# Power.net
KiCad netlist of a schematic drawn in Altium Designer
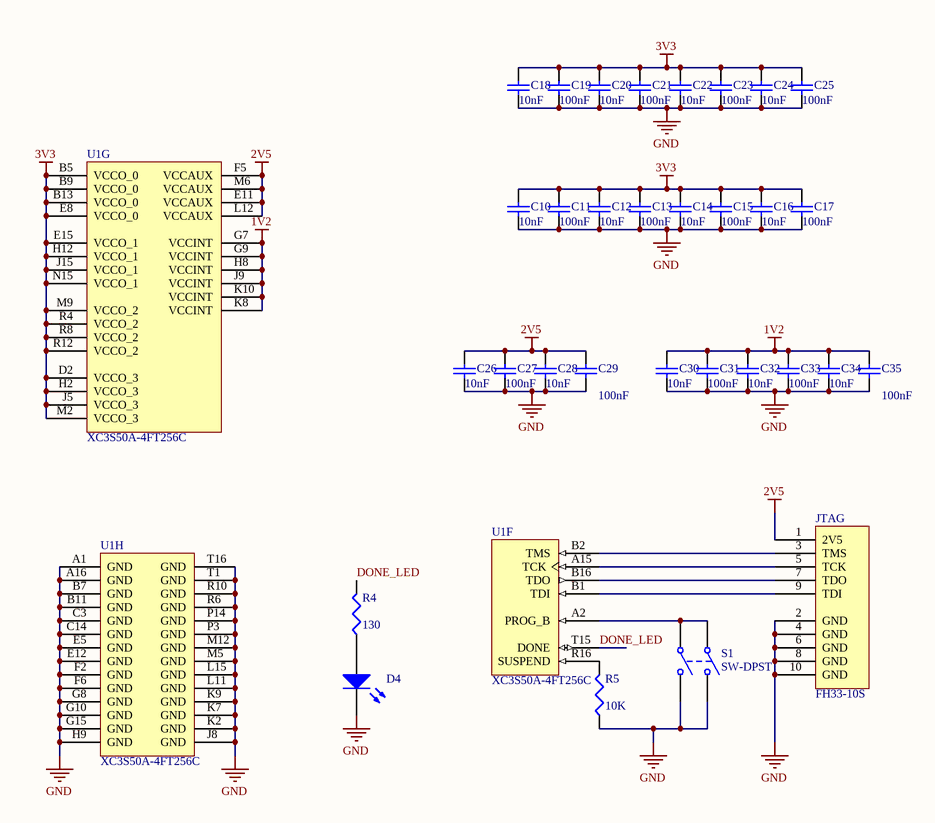
[diagram p0: Power.SchDoc]

(export (version "E")
  (design (tool "Eeschema 10.0.6"))
  (components
    (comp (ref "C10")
      (value "10nF")
      (footprint "0402")
      (description "Capacitor (Semiconductor SIM Model)")
      (fields (field (name "Comment") "Cap Semi") (field (name "PUBLISHER") "Altium Limited"))
      (libsource (lib "Miscellaneous Devices") (part "Cap Semi"))
    )
    (comp (ref "C11")
      (value "100nF")
      (footprint "0402")
      (description "Capacitor (Semiconductor SIM Model)")
      (fields (field (name "Comment") "Cap Semi") (field (name "PUBLISHER") "Altium Limited"))
      (libsource (lib "Miscellaneous Devices") (part "Cap Semi"))
    )
    (comp (ref "C12")
      (value "10nF")
      (footprint "0402")
      (description "Capacitor (Semiconductor SIM Model)")
      (fields (field (name "Comment") "Cap Semi") (field (name "PUBLISHER") "Altium Limited"))
      (libsource (lib "Miscellaneous Devices") (part "Cap Semi"))
    )
    (comp (ref "C13")
      (value "100nF")
      (footprint "0402")
      (description "Capacitor (Semiconductor SIM Model)")
      (fields (field (name "Comment") "Cap Semi") (field (name "PUBLISHER") "Altium Limited"))
      (libsource (lib "Miscellaneous Devices") (part "Cap Semi"))
    )
    (comp (ref "C14")
      (value "10nF")
      (footprint "0402")
      (description "Capacitor (Semiconductor SIM Model)")
      (fields (field (name "Comment") "Cap Semi") (field (name "PUBLISHER") "Altium Limited"))
      (libsource (lib "Miscellaneous Devices") (part "Cap Semi"))
    )
    (comp (ref "C15")
      (value "100nF")
      (footprint "0402")
      (description "Capacitor (Semiconductor SIM Model)")
      (fields (field (name "Comment") "Cap Semi") (field (name "PUBLISHER") "Altium Limited"))
      (libsource (lib "Miscellaneous Devices") (part "Cap Semi"))
    )
    (comp (ref "C16")
      (value "10nF")
      (footprint "0402")
      (description "Capacitor (Semiconductor SIM Model)")
      (fields (field (name "Comment") "Cap Semi") (field (name "PUBLISHER") "Altium Limited"))
      (libsource (lib "Miscellaneous Devices") (part "Cap Semi"))
    )
    (comp (ref "C17")
      (value "100nF")
      (footprint "0402")
      (description "Capacitor (Semiconductor SIM Model)")
      (fields (field (name "Comment") "Cap Semi") (field (name "PUBLISHER") "Altium Limited"))
      (libsource (lib "Miscellaneous Devices") (part "Cap Semi"))
    )
    (comp (ref "C18")
      (value "10nF")
      (footprint "0402")
      (description "Capacitor (Semiconductor SIM Model)")
      (fields (field (name "Comment") "Cap Semi") (field (name "PUBLISHER") "Altium Limited"))
      (libsource (lib "Miscellaneous Devices") (part "Cap Semi"))
    )
    (comp (ref "C19")
      (value "100nF")
      (footprint "0402")
      (description "Capacitor (Semiconductor SIM Model)")
      (fields (field (name "Comment") "Cap Semi") (field (name "PUBLISHER") "Altium Limited"))
      (libsource (lib "Miscellaneous Devices") (part "Cap Semi"))
    )
    (comp (ref "C20")
      (value "10nF")
      (footprint "0402")
      (description "Capacitor (Semiconductor SIM Model)")
      (fields (field (name "Comment") "Cap Semi") (field (name "PUBLISHER") "Altium Limited"))
      (libsource (lib "Miscellaneous Devices") (part "Cap Semi"))
    )
    (comp (ref "C21")
      (value "100nF")
      (footprint "0402")
      (description "Capacitor (Semiconductor SIM Model)")
      (fields (field (name "Comment") "Cap Semi") (field (name "PUBLISHER") "Altium Limited"))
      (libsource (lib "Miscellaneous Devices") (part "Cap Semi"))
    )
    (comp (ref "C22")
      (value "10nF")
      (footprint "0402")
      (description "Capacitor (Semiconductor SIM Model)")
      (fields (field (name "Comment") "Cap Semi") (field (name "PUBLISHER") "Altium Limited"))
      (libsource (lib "Miscellaneous Devices") (part "Cap Semi"))
    )
    (comp (ref "C23")
      (value "100nF")
      (footprint "0402")
      (description "Capacitor (Semiconductor SIM Model)")
      (fields (field (name "Comment") "Cap Semi") (field (name "PUBLISHER") "Altium Limited"))
      (libsource (lib "Miscellaneous Devices") (part "Cap Semi"))
    )
    (comp (ref "C24")
      (value "10nF")
      (footprint "0402")
      (description "Capacitor (Semiconductor SIM Model)")
      (fields (field (name "Comment") "Cap Semi") (field (name "PUBLISHER") "Altium Limited"))
      (libsource (lib "Miscellaneous Devices") (part "Cap Semi"))
    )
    (comp (ref "C25")
      (value "100nF")
      (footprint "0402")
      (description "Capacitor (Semiconductor SIM Model)")
      (fields (field (name "Comment") "Cap Semi") (field (name "PUBLISHER") "Altium Limited"))
      (libsource (lib "Miscellaneous Devices") (part "Cap Semi"))
    )
    (comp (ref "C26")
      (value "10nF")
      (footprint "0402")
      (description "Capacitor (Semiconductor SIM Model)")
      (fields (field (name "Comment") "Cap Semi") (field (name "PUBLISHER") "Altium Limited"))
      (libsource (lib "Miscellaneous Devices") (part "Cap Semi"))
    )
    (comp (ref "C27")
      (value "100nF")
      (footprint "0402")
      (description "Capacitor (Semiconductor SIM Model)")
      (fields (field (name "Comment") "Cap Semi") (field (name "PUBLISHER") "Altium Limited"))
      (libsource (lib "Miscellaneous Devices") (part "Cap Semi"))
    )
    (comp (ref "C28")
      (value "10nF")
      (footprint "0402")
      (description "Capacitor (Semiconductor SIM Model)")
      (fields (field (name "Comment") "Cap Semi") (field (name "PUBLISHER") "Altium Limited"))
      (libsource (lib "Miscellaneous Devices") (part "Cap Semi"))
    )
    (comp (ref "C29")
      (value "100nF")
      (footprint "0402")
      (description "Capacitor (Semiconductor SIM Model)")
      (fields (field (name "Comment") "Cap Semi") (field (name "PUBLISHER") "Altium Limited"))
      (libsource (lib "Miscellaneous Devices") (part "Cap Semi"))
    )
    (comp (ref "C30")
      (value "10nF")
      (footprint "0402")
      (description "Capacitor (Semiconductor SIM Model)")
      (fields (field (name "Comment") "Cap Semi") (field (name "PUBLISHER") "Altium Limited"))
      (libsource (lib "Miscellaneous Devices") (part "Cap Semi"))
    )
    (comp (ref "C31")
      (value "100nF")
      (footprint "0402")
      (description "Capacitor (Semiconductor SIM Model)")
      (fields (field (name "Comment") "Cap Semi") (field (name "PUBLISHER") "Altium Limited"))
      (libsource (lib "Miscellaneous Devices") (part "Cap Semi"))
    )
    (comp (ref "C32")
      (value "10nF")
      (footprint "0402")
      (description "Capacitor (Semiconductor SIM Model)")
      (fields (field (name "Comment") "Cap Semi") (field (name "PUBLISHER") "Altium Limited"))
      (libsource (lib "Miscellaneous Devices") (part "Cap Semi"))
    )
    (comp (ref "C33")
      (value "100nF")
      (footprint "0402")
      (description "Capacitor (Semiconductor SIM Model)")
      (fields (field (name "Comment") "Cap Semi") (field (name "PUBLISHER") "Altium Limited"))
      (libsource (lib "Miscellaneous Devices") (part "Cap Semi"))
    )
    (comp (ref "C34")
      (value "10nF")
      (footprint "0402")
      (description "Capacitor (Semiconductor SIM Model)")
      (fields (field (name "Comment") "Cap Semi") (field (name "PUBLISHER") "Altium Limited"))
      (libsource (lib "Miscellaneous Devices") (part "Cap Semi"))
    )
    (comp (ref "C35")
      (value "100nF")
      (footprint "0402")
      (description "Capacitor (Semiconductor SIM Model)")
      (fields (field (name "Comment") "Cap Semi") (field (name "PUBLISHER") "Altium Limited"))
      (libsource (lib "Miscellaneous Devices") (part "Cap Semi"))
    )
    (comp (ref "D4")
      (value "LED3")
      (footprint "1608[0603]")
      (description "Typical BLUE SiC LED")
      (fields (field (name "PUBLISHER") "Altium Limited"))
      (libsource (lib "Miscellaneous Devices") (part "LED3"))
    )
    (comp (ref "JTAG")
      (value "FH33-10S")
      (footprint "PCBComponent_1 - duplicate")
      (libsource (lib "FH33-10S-0.5SH(10)") (part "Component_1"))
    )
    (comp (ref "R4")
      (value "130")
      (footprint "J1-0603")
      (description "Resistor")
      (fields (field (name "Comment") "Res3") (field (name "PUBLISHER") "Altium Limited"))
      (libsource (lib "Miscellaneous Devices") (part "Res3"))
    )
    (comp (ref "R5")
      (value "10K")
      (footprint "J1-0603")
      (description "Resistor")
      (fields (field (name "Comment") "Res3") (field (name "PUBLISHER") "Altium Limited"))
      (libsource (lib "Miscellaneous Devices") (part "Res3"))
    )
    (comp (ref "S1")
      (value "SW-DPST")
      (footprint "DPST-4")
      (description "Double-Pole, Single-Throw Switch")
      (fields (field (name "PUBLISHER") "Altium Limited"))
      (libsource (lib "Miscellaneous Devices") (part "SW-DPST"))
    )
    (comp (ref "U1")
      (value "XC3S50A-4FT256C")
      (footprint "FT256")
      (fields (field (name "PUBLISHER") "Altium Limited"))
      (libsource (lib "Xilinx Spartan-3A") (part "XC3S50A-4FT256C"))
    )
  )
  (nets
    (net (code "1") (name "/DONE_LED") (class "Default")
      (node (ref "R4") (pin "2") (pinfunction "2_2") (pintype "passive"))
      (node (ref "U1") (pin "T15") (pinfunction "DONE_T15") (pintype "bidirectional"))
    )
    (net (code "2") (name "1V2") (class "Default")
      (node (ref "C30") (pin "1") (pinfunction "1_1") (pintype "passive"))
      (node (ref "C31") (pin "1") (pinfunction "1_1") (pintype "passive"))
      (node (ref "C32") (pin "1") (pinfunction "1_1") (pintype "passive"))
      (node (ref "C33") (pin "1") (pinfunction "1_1") (pintype "passive"))
      (node (ref "C34") (pin "1") (pinfunction "1_1") (pintype "passive"))
      (node (ref "C35") (pin "1") (pinfunction "1_1") (pintype "passive"))
      (node (ref "U1") (pin "G7") (pinfunction "VCCINT_G7") (pintype "power_in"))
      (node (ref "U1") (pin "G9") (pinfunction "VCCINT_G9") (pintype "power_in"))
      (node (ref "U1") (pin "H8") (pinfunction "VCCINT_H8") (pintype "power_in"))
      (node (ref "U1") (pin "J9") (pinfunction "VCCINT_J9") (pintype "power_in"))
      (node (ref "U1") (pin "K10") (pinfunction "VCCINT_K10") (pintype "power_in"))
      (node (ref "U1") (pin "K8") (pinfunction "VCCINT_K8") (pintype "power_in"))
    )
    (net (code "3") (name "2V5") (class "Default")
      (node (ref "C26") (pin "1") (pinfunction "1_1") (pintype "passive"))
      (node (ref "C27") (pin "1") (pinfunction "1_1") (pintype "passive"))
      (node (ref "C28") (pin "1") (pinfunction "1_1") (pintype "passive"))
      (node (ref "C29") (pin "1") (pinfunction "1_1") (pintype "passive"))
      (node (ref "JTAG") (pin "1") (pinfunction "2V5_1") (pintype "passive"))
      (node (ref "U1") (pin "E11") (pinfunction "VCCAUX_E11") (pintype "power_in"))
      (node (ref "U1") (pin "F5") (pinfunction "VCCAUX_F5") (pintype "power_in"))
      (node (ref "U1") (pin "L12") (pinfunction "VCCAUX_L12") (pintype "power_in"))
      (node (ref "U1") (pin "M6") (pinfunction "VCCAUX_M6") (pintype "power_in"))
    )
    (net (code "4") (name "3V3") (class "Default")
      (node (ref "C10") (pin "1") (pinfunction "1_1") (pintype "passive"))
      (node (ref "C11") (pin "1") (pinfunction "1_1") (pintype "passive"))
      (node (ref "C12") (pin "1") (pinfunction "1_1") (pintype "passive"))
      (node (ref "C13") (pin "1") (pinfunction "1_1") (pintype "passive"))
      (node (ref "C14") (pin "1") (pinfunction "1_1") (pintype "passive"))
      (node (ref "C15") (pin "1") (pinfunction "1_1") (pintype "passive"))
      (node (ref "C16") (pin "1") (pinfunction "1_1") (pintype "passive"))
      (node (ref "C17") (pin "1") (pinfunction "1_1") (pintype "passive"))
      (node (ref "C18") (pin "1") (pinfunction "1_1") (pintype "passive"))
      (node (ref "C19") (pin "1") (pinfunction "1_1") (pintype "passive"))
      (node (ref "C20") (pin "1") (pinfunction "1_1") (pintype "passive"))
      (node (ref "C21") (pin "1") (pinfunction "1_1") (pintype "passive"))
      (node (ref "C22") (pin "1") (pinfunction "1_1") (pintype "passive"))
      (node (ref "C23") (pin "1") (pinfunction "1_1") (pintype "passive"))
      (node (ref "C24") (pin "1") (pinfunction "1_1") (pintype "passive"))
      (node (ref "C25") (pin "1") (pinfunction "1_1") (pintype "passive"))
      (node (ref "U1") (pin "B13") (pinfunction "VCCO_0_B13") (pintype "power_in"))
      (node (ref "U1") (pin "B5") (pinfunction "VCCO_0_B5") (pintype "power_in"))
      (node (ref "U1") (pin "B9") (pinfunction "VCCO_0_B9") (pintype "power_in"))
      (node (ref "U1") (pin "D2") (pinfunction "VCCO_3_D2") (pintype "power_in"))
      (node (ref "U1") (pin "E15") (pinfunction "VCCO_1_E15") (pintype "power_in"))
      (node (ref "U1") (pin "E8") (pinfunction "VCCO_0_E8") (pintype "power_in"))
      (node (ref "U1") (pin "H12") (pinfunction "VCCO_1_H12") (pintype "power_in"))
      (node (ref "U1") (pin "H2") (pinfunction "VCCO_3_H2") (pintype "power_in"))
      (node (ref "U1") (pin "J15") (pinfunction "VCCO_1_J15") (pintype "power_in"))
      (node (ref "U1") (pin "J5") (pinfunction "VCCO_3_J5") (pintype "power_in"))
      (node (ref "U1") (pin "M2") (pinfunction "VCCO_3_M2") (pintype "power_in"))
      (node (ref "U1") (pin "M9") (pinfunction "VCCO_2_M9") (pintype "power_in"))
      (node (ref "U1") (pin "N15") (pinfunction "VCCO_1_N15") (pintype "power_in"))
      (node (ref "U1") (pin "R12") (pinfunction "VCCO_2_R12") (pintype "power_in"))
      (node (ref "U1") (pin "R4") (pinfunction "VCCO_2_R4") (pintype "power_in"))
      (node (ref "U1") (pin "R8") (pinfunction "VCCO_2_R8") (pintype "power_in"))
    )
    (net (code "5") (name "GND") (class "Default")
      (node (ref "C10") (pin "2") (pinfunction "2_2") (pintype "passive"))
      (node (ref "C11") (pin "2") (pinfunction "2_2") (pintype "passive"))
      (node (ref "C12") (pin "2") (pinfunction "2_2") (pintype "passive"))
      (node (ref "C13") (pin "2") (pinfunction "2_2") (pintype "passive"))
      (node (ref "C14") (pin "2") (pinfunction "2_2") (pintype "passive"))
      (node (ref "C15") (pin "2") (pinfunction "2_2") (pintype "passive"))
      (node (ref "C16") (pin "2") (pinfunction "2_2") (pintype "passive"))
      (node (ref "C17") (pin "2") (pinfunction "2_2") (pintype "passive"))
      (node (ref "C18") (pin "2") (pinfunction "2_2") (pintype "passive"))
      (node (ref "C19") (pin "2") (pinfunction "2_2") (pintype "passive"))
      (node (ref "C20") (pin "2") (pinfunction "2_2") (pintype "passive"))
      (node (ref "C21") (pin "2") (pinfunction "2_2") (pintype "passive"))
      (node (ref "C22") (pin "2") (pinfunction "2_2") (pintype "passive"))
      (node (ref "C23") (pin "2") (pinfunction "2_2") (pintype "passive"))
      (node (ref "C24") (pin "2") (pinfunction "2_2") (pintype "passive"))
      (node (ref "C25") (pin "2") (pinfunction "2_2") (pintype "passive"))
      (node (ref "C26") (pin "2") (pinfunction "2_2") (pintype "passive"))
      (node (ref "C27") (pin "2") (pinfunction "2_2") (pintype "passive"))
      (node (ref "C28") (pin "2") (pinfunction "2_2") (pintype "passive"))
      (node (ref "C29") (pin "2") (pinfunction "2_2") (pintype "passive"))
      (node (ref "C30") (pin "2") (pinfunction "2_2") (pintype "passive"))
      (node (ref "C31") (pin "2") (pinfunction "2_2") (pintype "passive"))
      (node (ref "C32") (pin "2") (pinfunction "2_2") (pintype "passive"))
      (node (ref "C33") (pin "2") (pinfunction "2_2") (pintype "passive"))
      (node (ref "C34") (pin "2") (pinfunction "2_2") (pintype "passive"))
      (node (ref "C35") (pin "2") (pinfunction "2_2") (pintype "passive"))
      (node (ref "D4") (pin "2") (pinfunction "K_2") (pintype "passive"))
      (node (ref "JTAG") (pin "10") (pinfunction "GND_10") (pintype "passive"))
      (node (ref "JTAG") (pin "2") (pinfunction "GND_2") (pintype "passive"))
      (node (ref "JTAG") (pin "4") (pinfunction "GND_4") (pintype "passive"))
      (node (ref "JTAG") (pin "6") (pinfunction "GND_6") (pintype "passive"))
      (node (ref "JTAG") (pin "8") (pinfunction "GND_8") (pintype "passive"))
      (node (ref "R5") (pin "1") (pinfunction "1_1") (pintype "passive"))
      (node (ref "S1") (pin "2") (pinfunction "NO1_2") (pintype "passive"))
      (node (ref "S1") (pin "4") (pinfunction "NO2_4") (pintype "passive"))
      (node (ref "U1") (pin "A1") (pinfunction "GND_A1") (pintype "power_in"))
      (node (ref "U1") (pin "A16") (pinfunction "GND_A16") (pintype "power_in"))
      (node (ref "U1") (pin "B11") (pinfunction "GND_B11") (pintype "power_in"))
      (node (ref "U1") (pin "B7") (pinfunction "GND_B7") (pintype "power_in"))
      (node (ref "U1") (pin "C14") (pinfunction "GND_C14") (pintype "power_in"))
      (node (ref "U1") (pin "C3") (pinfunction "GND_C3") (pintype "power_in"))
      (node (ref "U1") (pin "E12") (pinfunction "GND_E12") (pintype "power_in"))
      (node (ref "U1") (pin "E5") (pinfunction "GND_E5") (pintype "power_in"))
      (node (ref "U1") (pin "F2") (pinfunction "GND_F2") (pintype "power_in"))
      (node (ref "U1") (pin "F6") (pinfunction "GND_F6") (pintype "power_in"))
      (node (ref "U1") (pin "G10") (pinfunction "GND_G10") (pintype "power_in"))
      (node (ref "U1") (pin "G15") (pinfunction "GND_G15") (pintype "power_in"))
      (node (ref "U1") (pin "G8") (pinfunction "GND_G8") (pintype "power_in"))
      (node (ref "U1") (pin "H9") (pinfunction "GND_H9") (pintype "power_in"))
      (node (ref "U1") (pin "J8") (pinfunction "GND_J8") (pintype "power_in"))
      (node (ref "U1") (pin "K2") (pinfunction "GND_K2") (pintype "power_in"))
      (node (ref "U1") (pin "K7") (pinfunction "GND_K7") (pintype "power_in"))
      (node (ref "U1") (pin "K9") (pinfunction "GND_K9") (pintype "power_in"))
      (node (ref "U1") (pin "L11") (pinfunction "GND_L11") (pintype "power_in"))
      (node (ref "U1") (pin "L15") (pinfunction "GND_L15") (pintype "power_in"))
      (node (ref "U1") (pin "M12") (pinfunction "GND_M12") (pintype "power_in"))
      (node (ref "U1") (pin "M5") (pinfunction "GND_M5") (pintype "power_in"))
      (node (ref "U1") (pin "P14") (pinfunction "GND_P14") (pintype "power_in"))
      (node (ref "U1") (pin "P3") (pinfunction "GND_P3") (pintype "power_in"))
      (node (ref "U1") (pin "R10") (pinfunction "GND_R10") (pintype "power_in"))
      (node (ref "U1") (pin "R6") (pinfunction "GND_R6") (pintype "power_in"))
      (node (ref "U1") (pin "T1") (pinfunction "GND_T1") (pintype "power_in"))
      (node (ref "U1") (pin "T16") (pinfunction "GND_T16") (pintype "power_in"))
    )
    (net (code "6") (name "Net-(D4-A)") (class "Default")
      (node (ref "D4") (pin "1") (pinfunction "A_1") (pintype "passive"))
      (node (ref "R4") (pin "1") (pinfunction "1_1") (pintype "passive"))
    )
    (net (code "7") (name "Net-(JTAG-TCK)") (class "Default")
      (node (ref "JTAG") (pin "5") (pinfunction "TCK_5") (pintype "passive"))
      (node (ref "U1") (pin "A15") (pinfunction "TCK_A15") (pintype "input"))
    )
    (net (code "8") (name "Net-(JTAG-TDI)") (class "Default")
      (node (ref "JTAG") (pin "9") (pinfunction "TDI_9") (pintype "passive"))
      (node (ref "U1") (pin "B1") (pinfunction "TDI_B1") (pintype "input"))
    )
    (net (code "9") (name "Net-(JTAG-TDO)") (class "Default")
      (node (ref "JTAG") (pin "7") (pinfunction "TDO_7") (pintype "passive"))
      (node (ref "U1") (pin "B16") (pinfunction "TDO_B16") (pintype "output"))
    )
    (net (code "10") (name "Net-(JTAG-TMS)") (class "Default")
      (node (ref "JTAG") (pin "3") (pinfunction "TMS_3") (pintype "passive"))
      (node (ref "U1") (pin "B2") (pinfunction "TMS_B2") (pintype "input"))
    )
    (net (code "11") (name "Net-(S1-COMMON1)") (class "Default")
      (node (ref "S1") (pin "1") (pinfunction "COMMON1_1") (pintype "passive"))
      (node (ref "S1") (pin "3") (pinfunction "COMMON2_3") (pintype "passive"))
      (node (ref "U1") (pin "A2") (pinfunction "PROG_B_A2") (pintype "input"))
    )
    (net (code "12") (name "Net-(U1F-SUSPEND)") (class "Default")
      (node (ref "R5") (pin "2") (pinfunction "2_2") (pintype "passive"))
      (node (ref "U1") (pin "R16") (pinfunction "SUSPEND_R16") (pintype "input"))
    )
  )
)
